# BATTERY_GESTION.net
KiCad netlist of a schematic drawn in Altium Designer
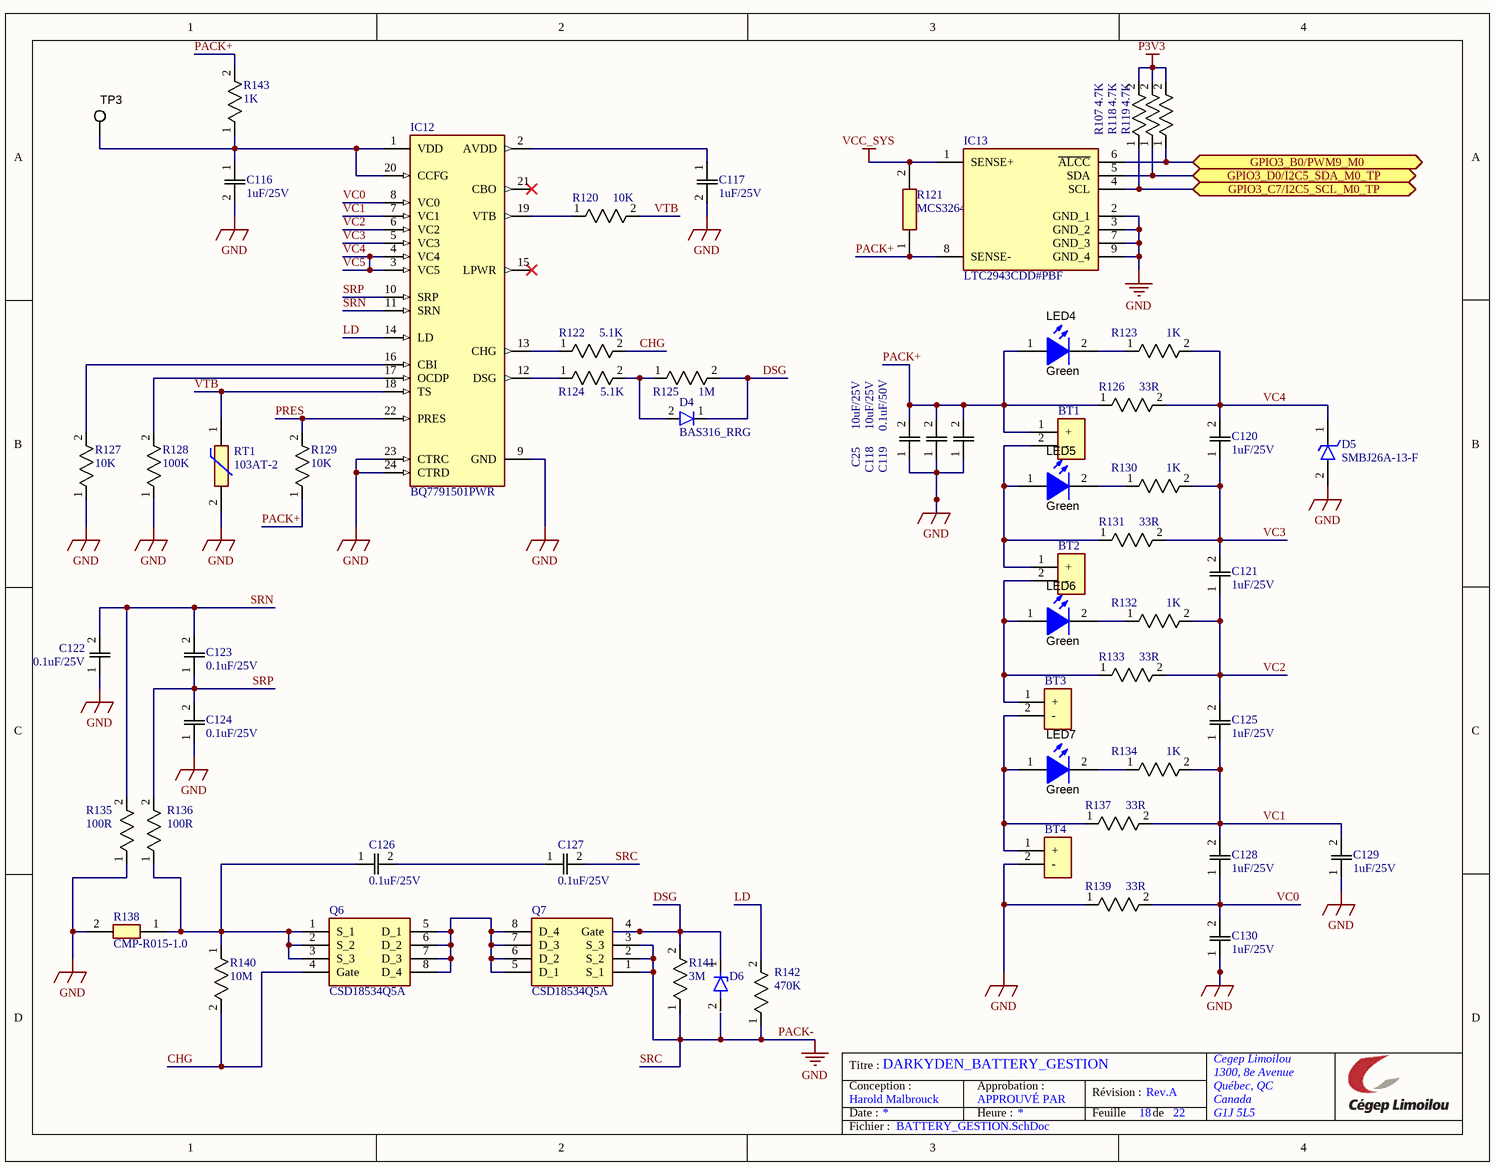
[diagram p0: BATTERY_GESTION.SchDoc]

(export (version "E")
  (design (tool "Eeschema 10.0.6"))
  (components
    (comp (ref "BT1")
      (value "0530480210")
      (footprint "SamacSys:SHDRRA2W35P0X125_1X2_425X550X350P")
      (description "Connector")
      (libsource (lib "SamacSys") (part "Header 1.25MM"))
    )
    (comp (ref "BT2")
      (value "0530480210")
      (footprint "SamacSys:SHDRRA2W35P0X125_1X2_425X550X350P")
      (description "Connector")
      (libsource (lib "SamacSys") (part "Header 1.25MM"))
    )
    (comp (ref "BT3")
      (value "0530480210")
      (footprint "SamacSys:SHDRRA2W35P0X125_1X2_425X550X350P")
      (description "Connector")
      (libsource (lib "SamacSys") (part "Header 1.25MM"))
    )
    (comp (ref "BT4")
      (value "0530480210")
      (footprint "SamacSys:SHDRRA2W35P0X125_1X2_425X550X350P")
      (description "Connector")
      (libsource (lib "SamacSys") (part "Header 1.25MM"))
    )
    (comp (ref "C25")
      (value "10uF/25V")
      (footprint "CAP_CC0805_YAG")
      (description "No Description Available")
      (libsource (lib "Capacitor_0805") (part "Capacitor_0805"))
    )
    (comp (ref "C116")
      (value "1uF/25V")
      (footprint "CAP_CC0805_YAG")
      (description "No Description Available")
      (libsource (lib "Capacitor_0805") (part "Capacitor_0805"))
    )
    (comp (ref "C117")
      (value "1uF/25V")
      (footprint "CAP_CC0805_YAG")
      (description "No Description Available")
      (libsource (lib "Capacitor_0805") (part "Capacitor_0805"))
    )
    (comp (ref "C118")
      (value "10uF/25V")
      (footprint "CAP_CC0805_YAG")
      (description "No Description Available")
      (libsource (lib "Capacitor_0805") (part "Capacitor_0805"))
    )
    (comp (ref "C119")
      (value "0.1uF/50V")
      (footprint "CAP_CC0805_YAG")
      (description "No Description Available")
      (libsource (lib "Capacitor_0805") (part "Capacitor_0805"))
    )
    (comp (ref "C120")
      (value "1uF/25V")
      (footprint "CAP_CC0805_YAG")
      (description "No Description Available")
      (libsource (lib "Capacitor_0805") (part "Capacitor_0805"))
    )
    (comp (ref "C121")
      (value "1uF/25V")
      (footprint "CAP_CC0805_YAG")
      (description "No Description Available")
      (libsource (lib "Capacitor_0805") (part "Capacitor_0805"))
    )
    (comp (ref "C122")
      (value "0.1uF/25V")
      (footprint "CAP_CC0805_YAG")
      (description "No Description Available")
      (libsource (lib "Capacitor_0805") (part "Capacitor_0805"))
    )
    (comp (ref "C123")
      (value "0.1uF/25V")
      (footprint "CAP_CC0805_YAG")
      (description "No Description Available")
      (libsource (lib "Capacitor_0805") (part "Capacitor_0805"))
    )
    (comp (ref "C124")
      (value "0.1uF/25V")
      (footprint "CAP_CC0805_YAG")
      (description "No Description Available")
      (libsource (lib "Capacitor_0805") (part "Capacitor_0805"))
    )
    (comp (ref "C125")
      (value "1uF/25V")
      (footprint "CAP_CC0805_YAG")
      (description "No Description Available")
      (libsource (lib "Capacitor_0805") (part "Capacitor_0805"))
    )
    (comp (ref "C126")
      (value "0.1uF/25V")
      (footprint "CAP_CC0805_YAG")
      (description "No Description Available")
      (libsource (lib "Capacitor_0805") (part "Capacitor_0805"))
    )
    (comp (ref "C127")
      (value "0.1uF/25V")
      (footprint "CAP_CC0805_YAG")
      (description "No Description Available")
      (libsource (lib "Capacitor_0805") (part "Capacitor_0805"))
    )
    (comp (ref "C128")
      (value "1uF/25V")
      (footprint "CAP_CC0805_YAG")
      (description "No Description Available")
      (libsource (lib "Capacitor_0805") (part "Capacitor_0805"))
    )
    (comp (ref "C129")
      (value "1uF/25V")
      (footprint "CAP_CC0805_YAG")
      (description "No Description Available")
      (libsource (lib "Capacitor_0805") (part "Capacitor_0805"))
    )
    (comp (ref "C130")
      (value "1uF/25V")
      (footprint "CAP_CC0805_YAG")
      (description "No Description Available")
      (libsource (lib "Capacitor_0805") (part "Capacitor_0805"))
    )
    (comp (ref "D4")
      (value "BAS316_RRG")
      (footprint "SamacSys:BAS316RRG")
      (description "Rectifier Diode Small Signal Switching 0.25A 4ns 2-Pin SOD-323 T/R")
      (fields
        (field (name "MANUFACTURER_PART_NUMBER") "BAS316 RRG")
        (field (name "MOUSER PART NUMBER") "821-BAS316RRG")
      )
      (libsource (lib "SamacSys") (part "BAS316_RRG"))
    )
    (comp (ref "D5")
      (value "SMBJ26A-13-F")
      (footprint "SamacSys:DIOM5336X250N")
      (description "TVS DIODE 26VWM 42.1VC SMB")
      (fields (field (name "MOUSER PART NUMBER") "621-SMBJ26A-13-F"))
      (libsource (lib "SamacSys") (part "SMBJ26A-13-F"))
    )
    (comp (ref "D6")
      (value "MMSZ5248B-7-F")
      (footprint "SamacSys:SOD3716X115N")
      (description "Zener Diode 18 V 500 mW ±5% Surface Mount SOD-123")
      (libsource (lib "SamacSys") (part "MMSZ5248B-7-F"))
    )
    (comp (ref "IC12")
      (value "BQ7791501PWR")
      (footprint "SamacSys:SOP65P640X120-24N")
      (description "/Polymer 3~5 TSSOP-24 Battery Management ICs ROHS")
      (fields
        (field (name "MOUSER PART NUMBER") "595-BQ7791501PWR")
        (field (name "MANUFACTURER") "Texas Instruments")
      )
      (libsource (lib "SamacSys") (part "BQ7791501PWR"))
    )
    (comp (ref "IC13")
      (value "LTC2943CDD#PBF")
      (footprint "SamacSys:SON50P300X300X80-9N-D")
      (description "LTC2943 - Multicell Battery Gas Gauge with Temperature, Voltage and Current Measurement")
      (fields
        (field (name "MOUSER PART NUMBER") "584-LTC2943CDD#PBF")
        (field (name "MANUFACTURER") "Analog Devices / Linear Technology")
      )
      (libsource (lib "SamacSys") (part "LTC2943CDD#PBF"))
    )
    (comp (ref "LED4")
      (value "Green")
      (footprint "LED_LTST-C190")
      (description "LED, Green, SMD")
      (fields (field (name "MANUFACTURER") "Lite-On") (field (name "PARTNUMBER") "LTST-C190GKT"))
      (libsource (lib "texas_instrument_power") (part "LED_Gr_SMD"))
    )
    (comp (ref "LED5")
      (value "Green")
      (footprint "LED_LTST-C190")
      (description "LED, Green, SMD")
      (fields (field (name "MANUFACTURER") "Lite-On") (field (name "PARTNUMBER") "LTST-C190GKT"))
      (libsource (lib "texas_instrument_power") (part "LED_Gr_SMD"))
    )
    (comp (ref "LED6")
      (value "Green")
      (footprint "LED_LTST-C190")
      (description "LED, Green, SMD")
      (fields (field (name "MANUFACTURER") "Lite-On") (field (name "PARTNUMBER") "LTST-C190GKT"))
      (libsource (lib "texas_instrument_power") (part "LED_Gr_SMD"))
    )
    (comp (ref "LED7")
      (value "Green")
      (footprint "LED_LTST-C190")
      (description "LED, Green, SMD")
      (fields (field (name "MANUFACTURER") "Lite-On") (field (name "PARTNUMBER") "LTST-C190GKT"))
      (libsource (lib "texas_instrument_power") (part "LED_Gr_SMD"))
    )
    (comp (ref "Q6")
      (value "CSD18534Q5A")
      (footprint "SamacSys:Q5A")
      (description "MOSFET N-Channel 60 V 13A (Ta), 50A (Tc) 3.1W (Ta), 77W (Tc) Surface Mount 8-VSONP (5x6)")
      (fields (field (name "MOUSER PART NUMBER") "595-CSD18534Q5A"))
      (libsource (lib "") (part "CSD18534Q5A_1"))
    )
    (comp (ref "Q7")
      (value "CSD18534Q5A")
      (footprint "SamacSys:Q5A")
      (description "MOSFET N-Channel 60 V 13A (Ta), 50A (Tc) 3.1W (Ta), 77W (Tc) Surface Mount 8-VSONP (5x6)")
      (fields (field (name "MOUSER PART NUMBER") "595-CSD18534Q5A"))
      (libsource (lib "SamacSys") (part "CSD18534Q5A"))
    )
    (comp (ref "R107")
      (value "4.7K")
      (footprint "RES_0816_SUS")
      (description "No Description Available")
      (libsource (lib "RES_SMD_0603") (part "RG1608P-104-B-T5"))
    )
    (comp (ref "R118")
      (value "4.7K")
      (footprint "RES_0816_SUS")
      (description "No Description Available")
      (libsource (lib "RES_SMD_0603") (part "RG1608P-104-B-T5"))
    )
    (comp (ref "R119")
      (value "4.7K")
      (footprint "RES_0816_SUS")
      (description "No Description Available")
      (libsource (lib "RES_SMD_0603") (part "RG1608P-104-B-T5"))
    )
    (comp (ref "R120")
      (value "10K")
      (footprint "RES_0816_SUS")
      (description "No Description Available")
      (libsource (lib "RES_SMD_0603") (part "RG1608P-104-B-T5"))
    )
    (comp (ref "R121")
      (value "MCS3264R010FER")
      (footprint "SamacSys:RESC6432X62N")
      (description "Res Metal Alloy 2512 0.01 Ohm 1% 2W 50ppm/ C Molded SMD T/R")
      (fields (field (name "MOUSER PART NUMBER") "588-MCS3264R010FER") (field (name "MANUFACTURER") "Ohmite"))
      (libsource (lib "SamacSys") (part "MCS3264R010FER"))
    )
    (comp (ref "R122")
      (value "5.1K")
      (footprint "RES_0816_SUS")
      (description "No Description Available")
      (libsource (lib "RES_SMD_0603") (part "RG1608P-104-B-T5"))
    )
    (comp (ref "R123")
      (value "1K")
      (footprint "RES_0816_SUS")
      (description "No Description Available")
      (libsource (lib "RES_SMD_0603") (part "RG1608P-104-B-T5"))
    )
    (comp (ref "R124")
      (value "5.1K")
      (footprint "RES_0816_SUS")
      (description "No Description Available")
      (libsource (lib "RES_SMD_0603") (part "RG1608P-104-B-T5"))
    )
    (comp (ref "R125")
      (value "1M")
      (footprint "RES_0816_SUS")
      (description "No Description Available")
      (libsource (lib "RES_SMD_0603") (part "RG1608P-104-B-T5"))
    )
    (comp (ref "R126")
      (value "33R")
      (footprint "RES_0816_SUS")
      (description "No Description Available")
      (libsource (lib "RES_SMD_0603") (part "RG1608P-104-B-T5"))
    )
    (comp (ref "R127")
      (value "10K")
      (footprint "RES_0816_SUS")
      (description "No Description Available")
      (libsource (lib "RES_SMD_0603") (part "RG1608P-104-B-T5"))
    )
    (comp (ref "R128")
      (value "100K")
      (footprint "RES_0816_SUS")
      (description "No Description Available")
      (libsource (lib "RES_SMD_0603") (part "RG1608P-104-B-T5"))
    )
    (comp (ref "R129")
      (value "10K")
      (footprint "RES_0816_SUS")
      (description "No Description Available")
      (libsource (lib "RES_SMD_0603") (part "RG1608P-104-B-T5"))
    )
    (comp (ref "R130")
      (value "1K")
      (footprint "RES_0816_SUS")
      (description "No Description Available")
      (libsource (lib "RES_SMD_0603") (part "RG1608P-104-B-T5"))
    )
    (comp (ref "R131")
      (value "33R")
      (footprint "RES_0816_SUS")
      (description "No Description Available")
      (libsource (lib "RES_SMD_0603") (part "RG1608P-104-B-T5"))
    )
    (comp (ref "R132")
      (value "1K")
      (footprint "RES_0816_SUS")
      (description "No Description Available")
      (libsource (lib "RES_SMD_0603") (part "RG1608P-104-B-T5"))
    )
    (comp (ref "R133")
      (value "33R")
      (footprint "RES_0816_SUS")
      (description "No Description Available")
      (libsource (lib "RES_SMD_0603") (part "RG1608P-104-B-T5"))
    )
    (comp (ref "R134")
      (value "1K")
      (footprint "RES_0816_SUS")
      (description "No Description Available")
      (libsource (lib "RES_SMD_0603") (part "RG1608P-104-B-T5"))
    )
    (comp (ref "R135")
      (value "100R")
      (footprint "RES_0816_SUS")
      (description "No Description Available")
      (libsource (lib "RES_SMD_0603") (part "RG1608P-104-B-T5"))
    )
    (comp (ref "R136")
      (value "100R")
      (footprint "RES_0816_SUS")
      (description "No Description Available")
      (libsource (lib "RES_SMD_0603") (part "RG1608P-104-B-T5"))
    )
    (comp (ref "R137")
      (value "33R")
      (footprint "RES_0816_SUS")
      (description "No Description Available")
      (libsource (lib "RES_SMD_0603") (part "RG1608P-104-B-T5"))
    )
    (comp (ref "R138")
      (value "CMP-R015-1.0")
      (footprint "SamacSys:RESC5025X70N")
      (description "Package 2010")
      (fields
        (field (name "MANUFACTURER_PART_NUMBER") "CRCW20100000Z0EFHP")
        (field (name "MOUSER PART NUMBER") "71-CRCW20100000Z0EFH")
      )
      (libsource (lib "SamacSys") (part "Resistor 2010"))
    )
    (comp (ref "R139")
      (value "33R")
      (footprint "RES_0816_SUS")
      (description "No Description Available")
      (libsource (lib "RES_SMD_0603") (part "RG1608P-104-B-T5"))
    )
    (comp (ref "R140")
      (value "10M")
      (footprint "RES_0816_SUS")
      (description "No Description Available")
      (libsource (lib "RES_SMD_0603") (part "RG1608P-104-B-T5"))
    )
    (comp (ref "R141")
      (value "3M")
      (footprint "RES_0816_SUS")
      (description "No Description Available")
      (libsource (lib "RES_SMD_0603") (part "RG1608P-104-B-T5"))
    )
    (comp (ref "R142")
      (value "470K")
      (footprint "RES_0816_SUS")
      (description "No Description Available")
      (libsource (lib "RES_SMD_0603") (part "RG1608P-104-B-T5"))
    )
    (comp (ref "R143")
      (value "1K")
      (footprint "RES_0816_SUS")
      (description "No Description Available")
      (libsource (lib "RES_SMD_0603") (part "RG1608P-104-B-T5"))
    )
    (comp (ref "RT1")
      (value "103AT-2")
      (footprint "SamacSys:103AT2")
      (description "NTC Thermistor 10k Bead")
      (fields (field (name "MOUSER PART NUMBER") "954-103AT-2"))
      (libsource (lib "SamacSys") (part "103AT-2"))
    )
    (comp (ref "TP3")
      (value "5016")
      (footprint "Testpoint_Keystone_Compact")
      (description "Test Point, Compact, SMT")
      (fields (field (name "MANUFACTURER") "Keystone") (field (name "PUBLISHER") "Texas Instruments"))
      (libsource (lib "texas_instrument_power") (part "TEST_POINT1"))
    )
  )
  (nets
    (net (code "1") (name "/CHG") (class "Default")
      (node (ref "Q6") (pin "4") (pinfunction "Gate_4") (pintype "passive"))
      (node (ref "R122") (pin "2") (pinfunction "2_2") (pintype "passive"))
      (node (ref "R140") (pin "2") (pinfunction "2_2") (pintype "passive"))
    )
    (net (code "2") (name "/DSG") (class "Default")
      (node (ref "D4") (pin "1") (pinfunction "K_1") (pintype "passive"))
      (node (ref "D6") (pin "1") (pinfunction "K_1") (pintype "passive"))
      (node (ref "Q7") (pin "4") (pinfunction "Gate_4") (pintype "passive"))
      (node (ref "R125") (pin "2") (pinfunction "2_2") (pintype "passive"))
      (node (ref "R141") (pin "2") (pinfunction "2_2") (pintype "passive"))
    )
    (net (code "3") (name "/GPIO3_B0{slash}PWM9_M0") (class "Default")
      (node (ref "IC13") (pin "6") (pinfunction "~{ALCC}_6") (pintype "passive"))
      (node (ref "R119") (pin "1") (pinfunction "1_1") (pintype "passive"))
    )
    (net (code "4") (name "/GPIO3_C7{slash}I2C5_SCL_M0_TP") (class "Default")
      (node (ref "IC13") (pin "4") (pinfunction "SCL_4") (pintype "passive"))
      (node (ref "R107") (pin "1") (pinfunction "1_1") (pintype "passive"))
    )
    (net (code "5") (name "/GPIO3_D0{slash}I2C5_SDA_M0_TP") (class "Default")
      (node (ref "IC13") (pin "5") (pinfunction "SDA_5") (pintype "passive"))
      (node (ref "R118") (pin "1") (pinfunction "1_1") (pintype "passive"))
    )
    (net (code "6") (name "/LD") (class "Default")
      (node (ref "IC12") (pin "14") (pinfunction "LD_14") (pintype "input"))
      (node (ref "R142") (pin "2") (pinfunction "2_2") (pintype "passive"))
    )
    (net (code "7") (name "/PACK+") (class "Default")
      (node (ref "BT1") (pin "1") (pinfunction "+_1") (pintype "passive"))
      (node (ref "C118") (pin "2") (pinfunction "2_2") (pintype "passive"))
      (node (ref "C119") (pin "2") (pinfunction "2_2") (pintype "passive"))
      (node (ref "C25") (pin "2") (pinfunction "2_2") (pintype "passive"))
      (node (ref "IC13") (pin "8") (pinfunction "SENSE-_8") (pintype "passive"))
      (node (ref "LED4") (pin "1") (pinfunction "A_1") (pintype "passive"))
      (node (ref "R121") (pin "1") (pinfunction "1_1") (pintype "passive"))
      (node (ref "R126") (pin "1") (pinfunction "1_1") (pintype "passive"))
      (node (ref "R129") (pin "1") (pinfunction "1_1") (pintype "passive"))
      (node (ref "R143") (pin "2") (pinfunction "2_2") (pintype "passive"))
    )
    (net (code "8") (name "/PRES") (class "Default")
      (node (ref "IC12") (pin "22") (pinfunction "PRES_22") (pintype "input"))
      (node (ref "R129") (pin "2") (pinfunction "2_2") (pintype "passive"))
    )
    (net (code "9") (name "/SRN") (class "Default")
      (node (ref "C122") (pin "2") (pinfunction "2_2") (pintype "passive"))
      (node (ref "C123") (pin "2") (pinfunction "2_2") (pintype "passive"))
      (node (ref "IC12") (pin "11") (pinfunction "SRN_11") (pintype "input"))
      (node (ref "R135") (pin "2") (pinfunction "2_2") (pintype "passive"))
    )
    (net (code "10") (name "/SRP") (class "Default")
      (node (ref "C123") (pin "1") (pinfunction "1_1") (pintype "passive"))
      (node (ref "C124") (pin "2") (pinfunction "2_2") (pintype "passive"))
      (node (ref "IC12") (pin "10") (pinfunction "SRP_10") (pintype "input"))
      (node (ref "R136") (pin "2") (pinfunction "2_2") (pintype "passive"))
    )
    (net (code "11") (name "/VC0") (class "Default")
      (node (ref "C128") (pin "1") (pinfunction "1_1") (pintype "passive"))
      (node (ref "C130") (pin "2") (pinfunction "2_2") (pintype "passive"))
      (node (ref "IC12") (pin "8") (pinfunction "VC0_8") (pintype "input"))
      (node (ref "R139") (pin "2") (pinfunction "2_2") (pintype "passive"))
    )
    (net (code "12") (name "/VC1") (class "Default")
      (node (ref "C125") (pin "1") (pinfunction "1_1") (pintype "passive"))
      (node (ref "C128") (pin "2") (pinfunction "2_2") (pintype "passive"))
      (node (ref "C129") (pin "2") (pinfunction "2_2") (pintype "passive"))
      (node (ref "IC12") (pin "7") (pinfunction "VC1_7") (pintype "input"))
      (node (ref "R134") (pin "2") (pinfunction "2_2") (pintype "passive"))
      (node (ref "R137") (pin "2") (pinfunction "2_2") (pintype "passive"))
    )
    (net (code "13") (name "/VC2") (class "Default")
      (node (ref "C121") (pin "1") (pinfunction "1_1") (pintype "passive"))
      (node (ref "C125") (pin "2") (pinfunction "2_2") (pintype "passive"))
      (node (ref "IC12") (pin "6") (pinfunction "VC2_6") (pintype "input"))
      (node (ref "R132") (pin "2") (pinfunction "2_2") (pintype "passive"))
      (node (ref "R133") (pin "2") (pinfunction "2_2") (pintype "passive"))
    )
    (net (code "14") (name "/VC3") (class "Default")
      (node (ref "C120") (pin "1") (pinfunction "1_1") (pintype "passive"))
      (node (ref "C121") (pin "2") (pinfunction "2_2") (pintype "passive"))
      (node (ref "IC12") (pin "5") (pinfunction "VC3_5") (pintype "input"))
      (node (ref "R130") (pin "2") (pinfunction "2_2") (pintype "passive"))
      (node (ref "R131") (pin "2") (pinfunction "2_2") (pintype "passive"))
    )
    (net (code "15") (name "/VC4") (class "Default")
      (node (ref "C120") (pin "2") (pinfunction "2_2") (pintype "passive"))
      (node (ref "D5") (pin "1") (pinfunction "K_1") (pintype "passive"))
      (node (ref "IC12") (pin "3") (pinfunction "VC5_3") (pintype "input"))
      (node (ref "IC12") (pin "4") (pinfunction "VC4_4") (pintype "input"))
      (node (ref "R123") (pin "2") (pinfunction "2_2") (pintype "passive"))
      (node (ref "R126") (pin "2") (pinfunction "2_2") (pintype "passive"))
    )
    (net (code "16") (name "/VTB") (class "Default")
      (node (ref "IC12") (pin "18") (pinfunction "TS_18") (pintype "input"))
      (node (ref "R120") (pin "2") (pinfunction "2_2") (pintype "passive"))
      (node (ref "RT1") (pin "1") (pinfunction "1_1") (pintype "passive"))
    )
    (net (code "17") (name "GND") (class "Default")
      (node (ref "BT4") (pin "2") (pinfunction "-_2") (pintype "passive"))
      (node (ref "C116") (pin "2") (pinfunction "2_2") (pintype "passive"))
      (node (ref "C117") (pin "2") (pinfunction "2_2") (pintype "passive"))
      (node (ref "C118") (pin "1") (pinfunction "1_1") (pintype "passive"))
      (node (ref "C119") (pin "1") (pinfunction "1_1") (pintype "passive"))
      (node (ref "C122") (pin "1") (pinfunction "1_1") (pintype "passive"))
      (node (ref "C124") (pin "1") (pinfunction "1_1") (pintype "passive"))
      (node (ref "C127") (pin "2") (pinfunction "2_2") (pintype "passive"))
      (node (ref "C129") (pin "1") (pinfunction "1_1") (pintype "passive"))
      (node (ref "C130") (pin "1") (pinfunction "1_1") (pintype "passive"))
      (node (ref "C25") (pin "1") (pinfunction "1_1") (pintype "passive"))
      (node (ref "D5") (pin "2") (pinfunction "A_2") (pintype "passive"))
      (node (ref "IC12") (pin "23") (pinfunction "CTRC_23") (pintype "input"))
      (node (ref "IC12") (pin "24") (pinfunction "CTRD_24") (pintype "input"))
      (node (ref "IC12") (pin "9") (pinfunction "GND_9") (pintype "passive"))
      (node (ref "IC13") (pin "2") (pinfunction "GND_1_2") (pintype "passive"))
      (node (ref "IC13") (pin "3") (pinfunction "GND_2_3") (pintype "passive"))
      (node (ref "IC13") (pin "7") (pinfunction "GND_3_7") (pintype "passive"))
      (node (ref "IC13") (pin "9") (pinfunction "GND_4_9") (pintype "passive"))
      (node (ref "Q7") (pin "1") (pinfunction "S_1_1") (pintype "passive"))
      (node (ref "Q7") (pin "2") (pinfunction "S_2_2") (pintype "passive"))
      (node (ref "Q7") (pin "3") (pinfunction "S_3_3") (pintype "passive"))
      (node (ref "R127") (pin "1") (pinfunction "1_1") (pintype "passive"))
      (node (ref "R128") (pin "1") (pinfunction "1_1") (pintype "passive"))
      (node (ref "R135") (pin "1") (pinfunction "1_1") (pintype "passive"))
      (node (ref "R138") (pin "2") (pinfunction "2_2") (pintype "passive"))
      (node (ref "R139") (pin "1") (pinfunction "1_1") (pintype "passive"))
      (node (ref "R141") (pin "1") (pinfunction "1_1") (pintype "passive"))
      (node (ref "R142") (pin "1") (pinfunction "1_1") (pintype "passive"))
      (node (ref "RT1") (pin "2") (pinfunction "2_2") (pintype "passive"))
    )
    (net (code "18") (name "Net-(BT1--)") (class "Default")
      (node (ref "BT1") (pin "2") (pinfunction "-_2") (pintype "passive"))
      (node (ref "BT2") (pin "1") (pinfunction "+_1") (pintype "passive"))
      (node (ref "LED5") (pin "1") (pinfunction "A_1") (pintype "passive"))
      (node (ref "R131") (pin "1") (pinfunction "1_1") (pintype "passive"))
    )
    (net (code "19") (name "Net-(BT2--)") (class "Default")
      (node (ref "BT2") (pin "2") (pinfunction "-_2") (pintype "passive"))
      (node (ref "BT3") (pin "1") (pinfunction "+_1") (pintype "passive"))
      (node (ref "LED6") (pin "1") (pinfunction "A_1") (pintype "passive"))
      (node (ref "R133") (pin "1") (pinfunction "1_1") (pintype "passive"))
    )
    (net (code "20") (name "Net-(BT3--)") (class "Default")
      (node (ref "BT3") (pin "2") (pinfunction "-_2") (pintype "passive"))
      (node (ref "BT4") (pin "1") (pinfunction "+_1") (pintype "passive"))
      (node (ref "LED7") (pin "1") (pinfunction "A_1") (pintype "passive"))
      (node (ref "R137") (pin "1") (pinfunction "1_1") (pintype "passive"))
    )
    (net (code "21") (name "Net-(C126-Pad2)") (class "Default")
      (node (ref "C126") (pin "2") (pinfunction "2_2") (pintype "passive"))
      (node (ref "C127") (pin "1") (pinfunction "1_1") (pintype "passive"))
    )
    (net (code "22") (name "Net-(D4-A)") (class "Default")
      (node (ref "D4") (pin "2") (pinfunction "A_2") (pintype "passive"))
      (node (ref "R124") (pin "2") (pinfunction "2_2") (pintype "passive"))
      (node (ref "R125") (pin "1") (pinfunction "1_1") (pintype "passive"))
    )
    (net (code "23") (name "Net-(IC12-AVDD)") (class "Default")
      (node (ref "C117") (pin "1") (pinfunction "1_1") (pintype "passive"))
      (node (ref "IC12") (pin "2") (pinfunction "AVDD_2") (pintype "output"))
    )
    (net (code "24") (name "Net-(IC12-CBI)") (class "Default")
      (node (ref "IC12") (pin "16") (pinfunction "CBI_16") (pintype "input"))
      (node (ref "R127") (pin "2") (pinfunction "2_2") (pintype "passive"))
    )
    (net (code "25") (name "Net-(IC12-CCFG)") (class "Default")
      (node (ref "C116") (pin "1") (pinfunction "1_1") (pintype "passive"))
      (node (ref "IC12") (pin "1") (pinfunction "VDD_1") (pintype "power_in"))
      (node (ref "IC12") (pin "20") (pinfunction "CCFG_20") (pintype "input"))
      (node (ref "R143") (pin "1") (pinfunction "1_1") (pintype "passive"))
      (node (ref "TP3") (pin "1") (pintype "passive"))
    )
    (net (code "26") (name "Net-(IC12-CHG)") (class "Default")
      (node (ref "IC12") (pin "13") (pinfunction "CHG_13") (pintype "output"))
      (node (ref "R122") (pin "1") (pinfunction "1_1") (pintype "passive"))
    )
    (net (code "27") (name "Net-(IC12-DSG)") (class "Default")
      (node (ref "IC12") (pin "12") (pinfunction "DSG_12") (pintype "output"))
      (node (ref "R124") (pin "1") (pinfunction "1_1") (pintype "passive"))
    )
    (net (code "28") (name "Net-(IC12-OCDP)") (class "Default")
      (node (ref "IC12") (pin "17") (pinfunction "OCDP_17") (pintype "input"))
      (node (ref "R128") (pin "2") (pinfunction "2_2") (pintype "passive"))
    )
    (net (code "29") (name "Net-(IC12-VTB)") (class "Default")
      (node (ref "IC12") (pin "19") (pinfunction "VTB_19") (pintype "output"))
      (node (ref "R120") (pin "1") (pinfunction "1_1") (pintype "passive"))
    )
    (net (code "30") (name "Net-(LED4-K)") (class "Default")
      (node (ref "LED4") (pin "2") (pinfunction "K_2") (pintype "passive"))
      (node (ref "R123") (pin "1") (pinfunction "1_1") (pintype "passive"))
    )
    (net (code "31") (name "Net-(LED5-K)") (class "Default")
      (node (ref "LED5") (pin "2") (pinfunction "K_2") (pintype "passive"))
      (node (ref "R130") (pin "1") (pinfunction "1_1") (pintype "passive"))
    )
    (net (code "32") (name "Net-(LED6-K)") (class "Default")
      (node (ref "LED6") (pin "2") (pinfunction "K_2") (pintype "passive"))
      (node (ref "R132") (pin "1") (pinfunction "1_1") (pintype "passive"))
    )
    (net (code "33") (name "Net-(LED7-K)") (class "Default")
      (node (ref "LED7") (pin "2") (pinfunction "K_2") (pintype "passive"))
      (node (ref "R134") (pin "1") (pinfunction "1_1") (pintype "passive"))
    )
    (net (code "34") (name "Net-(Q6-D_1)") (class "Default")
      (node (ref "Q6") (pin "5") (pinfunction "D_1_5") (pintype "passive"))
      (node (ref "Q6") (pin "6") (pinfunction "D_2_6") (pintype "passive"))
      (node (ref "Q6") (pin "7") (pinfunction "D_3_7") (pintype "passive"))
      (node (ref "Q6") (pin "8") (pinfunction "D_4_8") (pintype "passive"))
      (node (ref "Q7") (pin "5") (pinfunction "D_1_5") (pintype "passive"))
      (node (ref "Q7") (pin "6") (pinfunction "D_2_6") (pintype "passive"))
      (node (ref "Q7") (pin "7") (pinfunction "D_3_7") (pintype "passive"))
      (node (ref "Q7") (pin "8") (pinfunction "D_4_8") (pintype "passive"))
    )
    (net (code "35") (name "Net-(Q6-S_1)") (class "Default")
      (node (ref "C126") (pin "1") (pinfunction "1_1") (pintype "passive"))
      (node (ref "Q6") (pin "1") (pinfunction "S_1_1") (pintype "passive"))
      (node (ref "Q6") (pin "2") (pinfunction "S_2_2") (pintype "passive"))
      (node (ref "Q6") (pin "3") (pinfunction "S_3_3") (pintype "passive"))
      (node (ref "R136") (pin "1") (pinfunction "1_1") (pintype "passive"))
      (node (ref "R138") (pin "1") (pinfunction "1_1") (pintype "passive"))
      (node (ref "R140") (pin "1") (pinfunction "1_1") (pintype "passive"))
    )
    (net (code "36") (name "P3V3") (class "Default")
      (node (ref "R107") (pin "2") (pinfunction "2_2") (pintype "passive"))
      (node (ref "R118") (pin "2") (pinfunction "2_2") (pintype "passive"))
      (node (ref "R119") (pin "2") (pinfunction "2_2") (pintype "passive"))
    )
    (net (code "37") (name "VCC_SYS") (class "Default")
      (node (ref "IC13") (pin "1") (pinfunction "SENSE+_1") (pintype "passive"))
      (node (ref "R121") (pin "2") (pinfunction "2_2") (pintype "passive"))
    )
    (net (code "38") (name "unconnected-(D6-A-Pad2)") (class "Default")
      (node (ref "D6") (pin "2") (pinfunction "A_2") (pintype "passive"))
    )
    (net (code "39") (name "unconnected-(IC12-CBO-Pad21)") (class "Default")
      (node (ref "IC12") (pin "21") (pinfunction "CBO_21") (pintype "output+no_connect"))
    )
    (net (code "40") (name "unconnected-(IC12-LPWR-Pad15)") (class "Default")
      (node (ref "IC12") (pin "15") (pinfunction "LPWR_15") (pintype "output+no_connect"))
    )
  )
)
